# RF_FRONTEND.net
KiCad netlist of a schematic drawn in Altium Designer
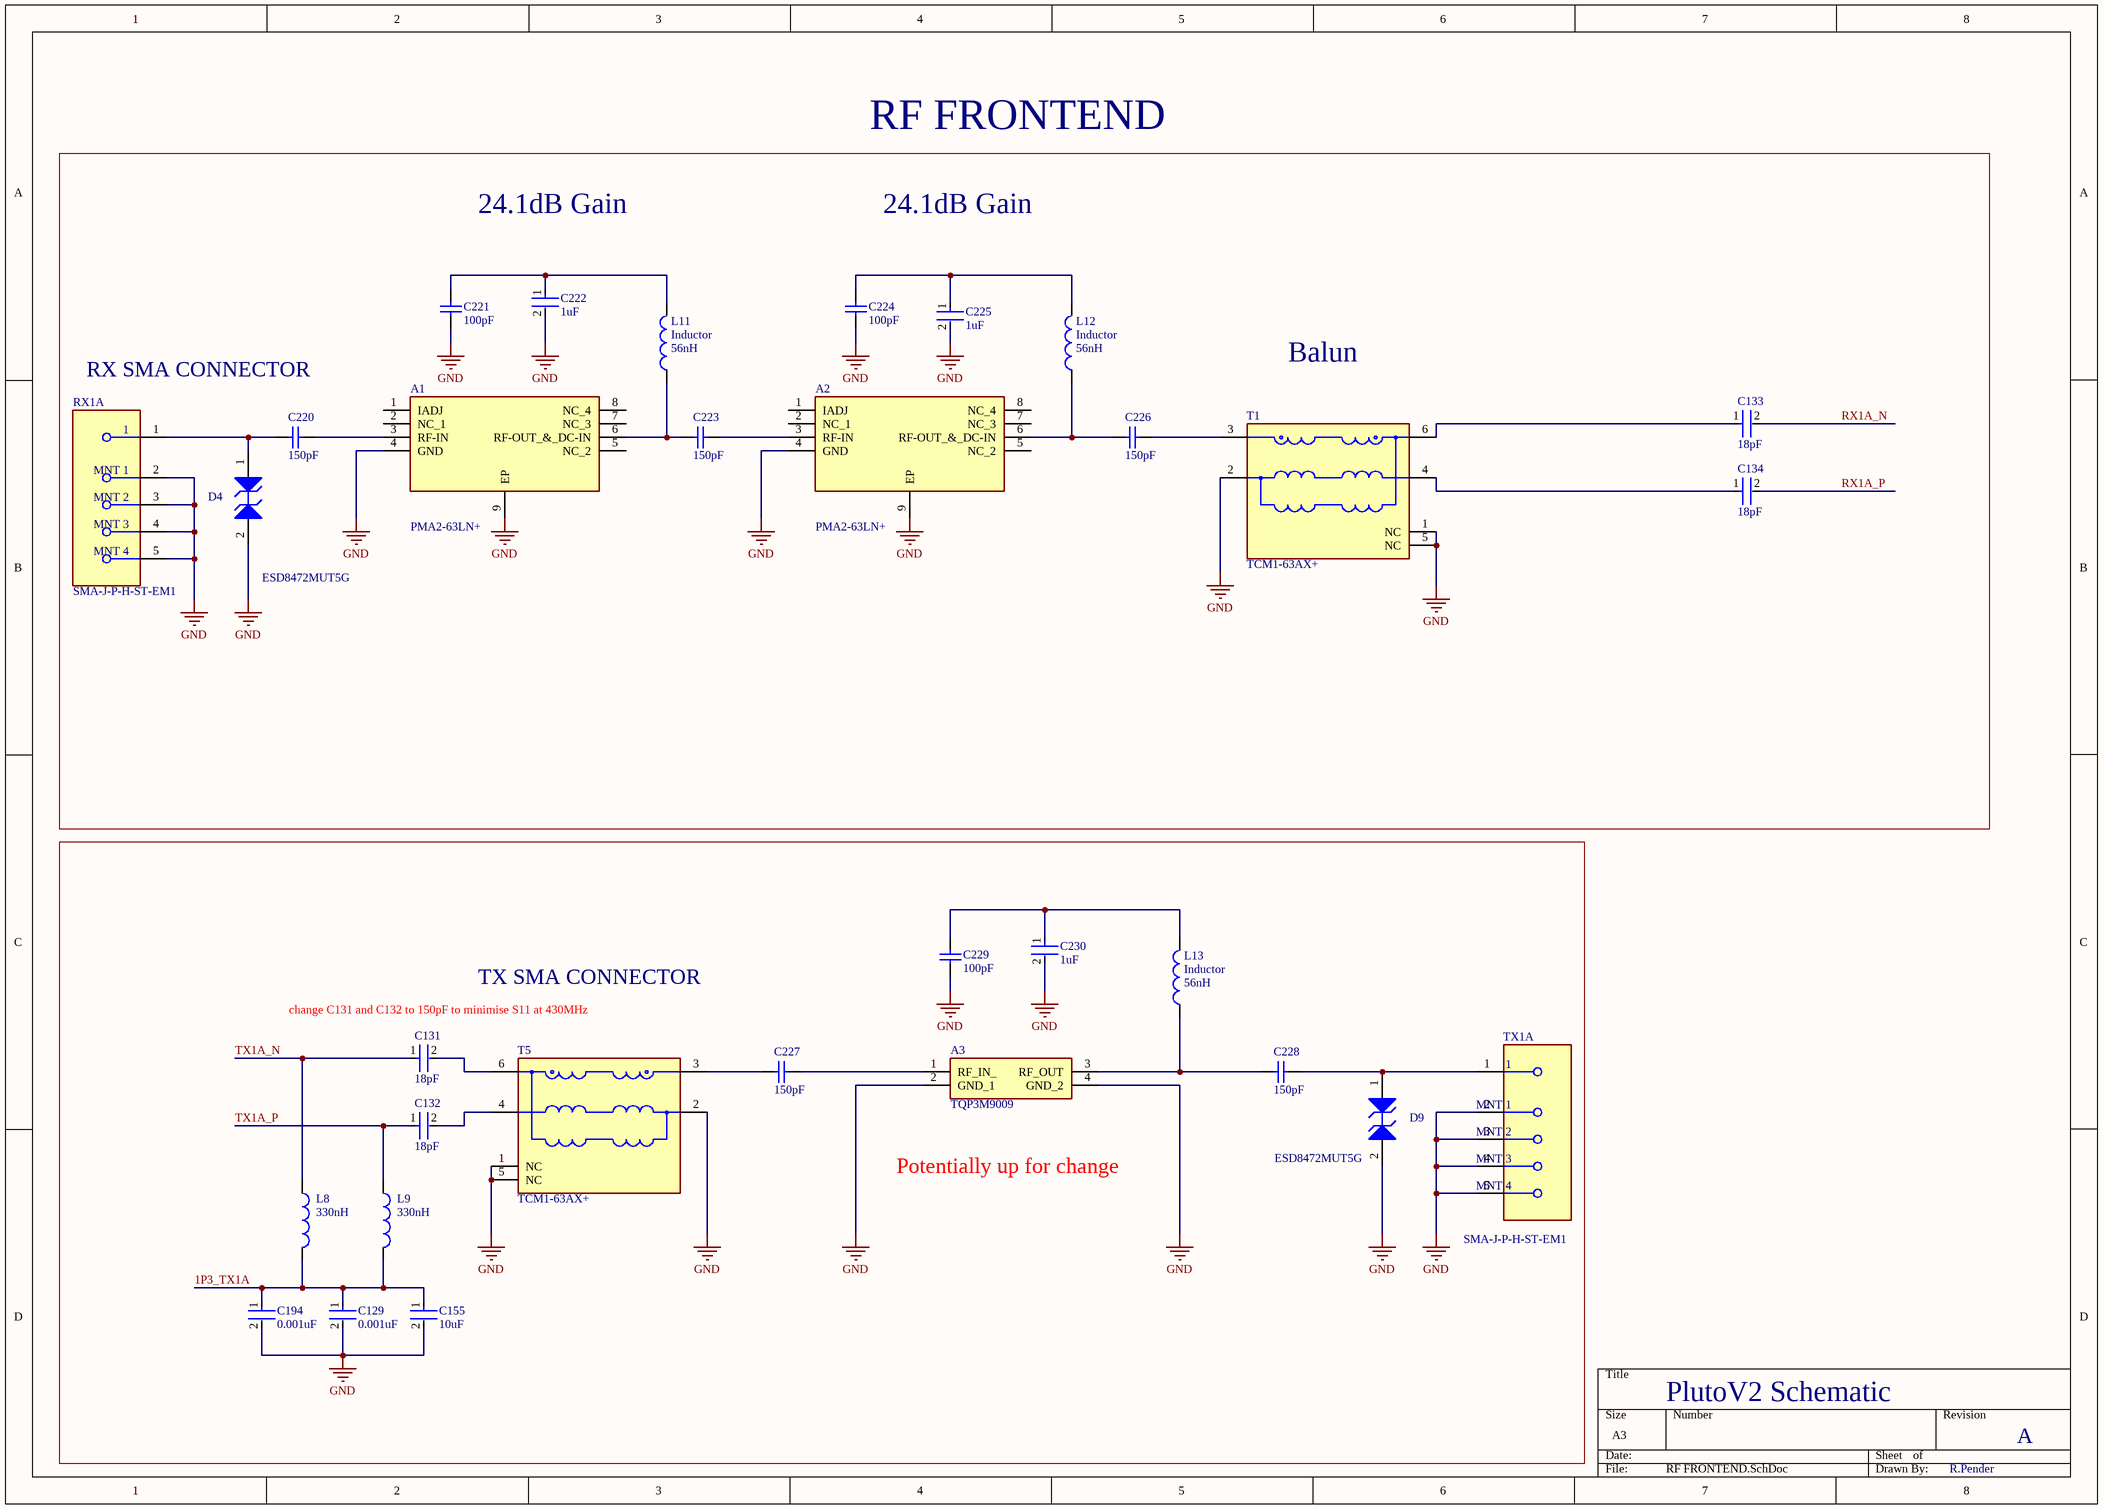
[diagram p0: RF FRONTEND.SchDoc]

(export (version "E")
  (design (tool "Eeschema 10.0.6"))
  (components
    (comp (ref "A1")
      (value "PMA2-63LN+")
      (footprint "SamacSys:SON50P200X200X105-9N")
      (description "Integrated Circuit")
      (libsource (lib "*") (part "PMA2-63LN+"))
    )
    (comp (ref "A2")
      (value "PMA2-63LN+")
      (footprint "SamacSys:SON50P200X200X105-9N")
      (description "Integrated Circuit")
      (libsource (lib "*") (part "PMA2-63LN+"))
    )
    (comp (ref "A3")
      (value "TQP3M9009")
      (footprint "SamacSys:TQP3M9009")
      (description "Integrated Circuit")
      (libsource (lib "*") (part "TQP3M9009"))
    )
    (comp (ref "C129")
      (value "0.001uF")
      (footprint "FP-GRM033-0_03-MFG")
      (description "Chip Multilayer Ceramic Capacitors for General Purpose, 0201, 1000pF, X7R, 15%, 10%, 25V")
      (fields (field (name "TOLERANCE") "10%") (field (name "VOLTAGE") "25V"))
      (libsource (lib "Altium Content Vault") (part "b4654b650e69147ec39a6b967a45e02"))
    )
    (comp (ref "C131")
      (value "18pF")
      (footprint "FP-GRM033-0_03-IPC_A")
      (description "Chip Multilayer Ceramic Capacitors for General Purpose, 0201, 18pF, C0G, 30ppm/°C, 5%, 50V")
      (fields (field (name "TOLERANCE") "5%") (field (name "VOLTAGE") "50V"))
      (libsource (lib "Altium Content Vault") (part "b4654b650e69147ec39a6b967a45e02"))
    )
    (comp (ref "C132")
      (value "18pF")
      (footprint "FP-GRM033-0_03-IPC_A")
      (description "Chip Multilayer Ceramic Capacitors for General Purpose, 0201, 18pF, C0G, 30ppm/°C, 5%, 50V")
      (fields (field (name "TOLERANCE") "5%") (field (name "VOLTAGE") "50V"))
      (libsource (lib "Altium Content Vault") (part "b4654b650e69147ec39a6b967a45e02"))
    )
    (comp (ref "C133")
      (value "18pF")
      (footprint "FP-GRM033-0_03-IPC_A")
      (description "Chip Multilayer Ceramic Capacitors for General Purpose, 0201, 18pF, C0G, 30ppm/°C, 5%, 50V")
      (fields (field (name "TOLERANCE") "5%") (field (name "VOLTAGE") "50V"))
      (libsource (lib "Altium Content Vault") (part "b4654b650e69147ec39a6b967a45e02"))
    )
    (comp (ref "C134")
      (value "18pF")
      (footprint "FP-GRM033-0_03-IPC_A")
      (description "Chip Multilayer Ceramic Capacitors for General Purpose, 0201, 18pF, C0G, 30ppm/°C, 5%, 50V")
      (fields (field (name "TOLERANCE") "5%") (field (name "VOLTAGE") "50V"))
      (libsource (lib "Altium Content Vault") (part "b4654b650e69147ec39a6b967a45e02"))
    )
    (comp (ref "C155")
      (value "10uF")
      (footprint "FP-GRM188-0_1-e0_2_0_55-IPC_C")
      (description "Chip Multilayer Ceramic Capacitors for General Purpose, 0603, 10uF, X5R, 15%, 20%, 6.3V")
      (fields (field (name "VOLTAGE") "6.3V") (field (name "TOLERANCE") "20%"))
      (libsource (lib "Altium Content Vault") (part "02cd4be3c70576c341d710602a673aa"))
    )
    (comp (ref "C194")
      (value "0.001uF")
      (footprint "FP-GRM033-0_03-MFG")
      (description "Chip Multilayer Ceramic Capacitors for General Purpose, 0201, 1000pF, X7R, 15%, 10%, 25V")
      (fields (field (name "TOLERANCE") "10%") (field (name "VOLTAGE") "25V"))
      (libsource (lib "Altium Content Vault") (part "b4654b650e69147ec39a6b967a45e02"))
    )
    (comp (ref "C220")
      (value "150pF")
      (footprint "CAPC1005X55X25ML05T10")
      (fields (field (name "MANUFACTURER") "Murata") (field (name "PART NUMBER") "GRM1555C1H151JA01D"))
      (libsource (lib "Altium Content Vault") (part "CAP"))
    )
    (comp (ref "C221")
      (value "100pF")
      (footprint "CAPC1005X55X25ML05T10")
      (fields (field (name "MANUFACTURER") "Murata") (field (name "PART NUMBER") "GRM1555C1H101JA01D"))
      (libsource (lib "Altium Content Vault") (part "CAP"))
    )
    (comp (ref "C222")
      (value "1uF")
      (footprint "FP-GRM155-0_05-IPC_B")
      (description "Chip Multilayer Ceramic Capacitors for General Purpose, 0402, 1.0uF, X5R, 15%, 10%, 25V")
      (fields (field (name "VOLTAGE") "25V") (field (name "TOLERANCE") "10%"))
      (libsource (lib "Altium Content Vault") (part "02cd4be3c70576c341d710602a673aa"))
    )
    (comp (ref "C223")
      (value "150pF")
      (footprint "CAPC1005X55X25ML05T10")
      (fields (field (name "MANUFACTURER") "Murata") (field (name "PART NUMBER") "GRM1555C1H151JA01D"))
      (libsource (lib "Altium Content Vault") (part "CAP"))
    )
    (comp (ref "C224")
      (value "100pF")
      (footprint "CAPC1005X55X25ML05T10")
      (fields (field (name "MANUFACTURER") "Murata") (field (name "PART NUMBER") "GRM1555C1H101JA01D"))
      (libsource (lib "Altium Content Vault") (part "CAP"))
    )
    (comp (ref "C225")
      (value "1uF")
      (footprint "FP-GRM155-0_05-IPC_B")
      (description "Chip Multilayer Ceramic Capacitors for General Purpose, 0402, 1.0uF, X5R, 15%, 10%, 25V")
      (fields (field (name "VOLTAGE") "25V") (field (name "TOLERANCE") "10%"))
      (libsource (lib "Altium Content Vault") (part "02cd4be3c70576c341d710602a673aa"))
    )
    (comp (ref "C226")
      (value "150pF")
      (footprint "CAPC1005X55X25LL05T10")
      (fields (field (name "MANUFACTURER") "Murata") (field (name "PART NUMBER") "GRM1555C1H151JA01D"))
      (libsource (lib "Altium Content Vault") (part "CAP"))
    )
    (comp (ref "C227")
      (value "150pF")
      (footprint "CAPC1005X55X25LL05T10")
      (fields (field (name "MANUFACTURER") "Murata") (field (name "PART NUMBER") "GRM1555C1H151JA01D"))
      (libsource (lib "Altium Content Vault") (part "CAP"))
    )
    (comp (ref "C228")
      (value "150pF")
      (footprint "CAPC1005X55X25LL05T10")
      (fields (field (name "MANUFACTURER") "Murata") (field (name "PART NUMBER") "GRM1555C1H151JA01D"))
      (libsource (lib "Altium Content Vault") (part "CAP"))
    )
    (comp (ref "C229")
      (value "100pF")
      (footprint "CAPC1005X55X25ML05T10")
      (fields (field (name "MANUFACTURER") "Murata") (field (name "PART NUMBER") "GRM1555C1H101JA01D"))
      (libsource (lib "Altium Content Vault") (part "CAP"))
    )
    (comp (ref "C230")
      (value "1uF")
      (footprint "FP-GRM155-0_05-IPC_B")
      (description "Chip Multilayer Ceramic Capacitors for General Purpose, 0402, 1.0uF, X5R, 15%, 10%, 25V")
      (fields (field (name "VOLTAGE") "25V") (field (name "TOLERANCE") "10%"))
      (libsource (lib "Altium Content Vault") (part "02cd4be3c70576c341d710602a673aa"))
    )
    (comp (ref "D4")
      (value "ESD8472MUT5G")
      (footprint "ONSC-X3DFN-2-152AF-01_V")
      (fields (field (name "MANUFACTURER") "On Semiconductor"))
      (libsource (lib "Altium Content Vault") (part "ONSC-A1A2-2"))
    )
    (comp (ref "D9")
      (value "ESD8472MUT5G")
      (footprint "ONSC-X3DFN-2-152AF-01_V")
      (fields (field (name "MANUFACTURER") "On Semiconductor"))
      (libsource (lib "Altium Content Vault") (part "ONSC-A1A2-2"))
    )
    (comp (ref "L8")
      (value "330nH")
      (footprint "INDC2317X140N")
      (description "Inductor")
      (fields (field (name "PUBLISHER") "Altium Limited"))
      (libsource (lib "Miscellaneous Devices") (part "Inductor"))
    )
    (comp (ref "L9")
      (value "330nH")
      (footprint "INDC2317X140N")
      (description "Inductor")
      (fields (field (name "PUBLISHER") "Altium Limited"))
      (libsource (lib "Miscellaneous Devices") (part "Inductor"))
    )
    (comp (ref "L11")
      (value "Inductor")
      (footprint "0402-A")
      (fields (field (name "ALTIUM_VALUE") "56nH") (field (name "PUBLISHER") "Altium Limited"))
      (libsource (lib "Miscellaneous Devices") (part "Inductor"))
    )
    (comp (ref "L12")
      (value "Inductor")
      (footprint "0402-A")
      (fields (field (name "ALTIUM_VALUE") "56nH") (field (name "PUBLISHER") "Altium Limited"))
      (libsource (lib "Miscellaneous Devices") (part "Inductor"))
    )
    (comp (ref "L13")
      (value "Inductor")
      (footprint "0402-A")
      (fields (field (name "ALTIUM_VALUE") "56nH") (field (name "PUBLISHER") "Altium Limited"))
      (libsource (lib "Miscellaneous Devices") (part "Inductor"))
    )
    (comp (ref "RX1A")
      (value "SMA-J-P-H-ST-EM1")
      (footprint "FP-SMA-J-P-H-ST-EM1-MFG")
      (description "CONN SMA JACK STR 50OHM EDGE MNT")
      (libsource (lib "Altium Content Vault") (part "c65b8a639cdaef1819ea20b5466f8fa"))
    )
    (comp (ref "T1")
      (value "TCM1-63AX+")
      (footprint "FP-TCM1-63AX+-MFG")
      (description "1:1 CORE & WIRE Transformer, 10 - 6000 MHz, 50Ω")
      (fields
        (field (name "MANUFACTURER") "Mini-Circuits")
        (field (name "OCTOPART") "https://octopart.com/tcm1-63ax%2B-mini-circuits-107315723")
      )
      (libsource (lib "") (part "572340aedd709dbafee1a1d3331a406_1"))
    )
    (comp (ref "T5")
      (value "TCM1-63AX+")
      (footprint "FP-TCM1-63AX+-MFG")
      (description "1:1 CORE & WIRE Transformer, 10 - 6000 MHz, 50Ω")
      (fields
        (field (name "MANUFACTURER") "Mini-Circuits")
        (field (name "OCTOPART") "https://octopart.com/tcm1-63ax%2B-mini-circuits-107315723")
      )
      (libsource (lib "Altium Content Vault") (part "572340aedd709dbafee1a1d3331a406"))
    )
    (comp (ref "TX1A")
      (value "SMA-J-P-H-ST-EM1")
      (footprint "FP-SMA-J-P-H-ST-EM1-MFG")
      (description "CONN SMA JACK STR 50OHM EDGE MNT")
      (libsource (lib "") (part "c65b8a639cdaef1819ea20b5466f8fa_1"))
    )
  )
  (nets
    (net (code "1") (name "/1P3_TX1A") (class "Default")
      (node (ref "C129") (pin "1") (pinfunction "1_1") (pintype "passive"))
      (node (ref "C155") (pin "1") (pinfunction "1_1") (pintype "passive"))
      (node (ref "C194") (pin "1") (pinfunction "1_1") (pintype "passive"))
      (node (ref "L8") (pin "2") (pinfunction "2_2") (pintype "passive"))
      (node (ref "L9") (pin "2") (pinfunction "2_2") (pintype "passive"))
    )
    (net (code "2") (name "/RX1A_N") (class "Default")
      (node (ref "C133") (pin "2") (pinfunction "2_2") (pintype "passive"))
    )
    (net (code "3") (name "/RX1A_P") (class "Default")
      (node (ref "C134") (pin "2") (pinfunction "2_2") (pintype "passive"))
    )
    (net (code "4") (name "/TX1A_N") (class "Default")
      (node (ref "C131") (pin "1") (pinfunction "1_1") (pintype "passive"))
      (node (ref "L8") (pin "1") (pinfunction "1_1") (pintype "passive"))
    )
    (net (code "5") (name "/TX1A_P") (class "Default")
      (node (ref "C132") (pin "1") (pinfunction "1_1") (pintype "passive"))
      (node (ref "L9") (pin "1") (pinfunction "1_1") (pintype "passive"))
    )
    (net (code "6") (name "GND") (class "Default")
      (node (ref "A1") (pin "4") (pinfunction "GND_4") (pintype "passive"))
      (node (ref "A1") (pin "9") (pinfunction "EP_9") (pintype "passive"))
      (node (ref "A2") (pin "4") (pinfunction "GND_4") (pintype "passive"))
      (node (ref "A2") (pin "9") (pinfunction "EP_9") (pintype "passive"))
      (node (ref "A3") (pin "2") (pinfunction "GND_1_2") (pintype "passive"))
      (node (ref "A3") (pin "4") (pinfunction "GND_2_4") (pintype "passive"))
      (node (ref "C129") (pin "2") (pinfunction "2_2") (pintype "passive"))
      (node (ref "C155") (pin "2") (pinfunction "2_2") (pintype "passive"))
      (node (ref "C194") (pin "2") (pinfunction "2_2") (pintype "passive"))
      (node (ref "C221") (pin "2") (pinfunction "2_2") (pintype "passive"))
      (node (ref "C222") (pin "2") (pinfunction "2_2") (pintype "passive"))
      (node (ref "C224") (pin "2") (pinfunction "2_2") (pintype "passive"))
      (node (ref "C225") (pin "2") (pinfunction "2_2") (pintype "passive"))
      (node (ref "C229") (pin "2") (pinfunction "2_2") (pintype "passive"))
      (node (ref "C230") (pin "2") (pinfunction "2_2") (pintype "passive"))
      (node (ref "D4") (pin "2") (pinfunction "A2_2") (pintype "passive"))
      (node (ref "D9") (pin "2") (pinfunction "A2_2") (pintype "passive"))
      (node (ref "RX1A") (pin "2") (pinfunction "MNT_1_2") (pintype "passive"))
      (node (ref "RX1A") (pin "3") (pinfunction "MNT_2_3") (pintype "passive"))
      (node (ref "RX1A") (pin "4") (pinfunction "MNT_3_4") (pintype "passive"))
      (node (ref "RX1A") (pin "5") (pinfunction "MNT_4_5") (pintype "passive"))
      (node (ref "T1") (pin "1") (pinfunction "NC_1") (pintype "passive"))
      (node (ref "T1") (pin "2") (pinfunction "GND_2") (pintype "passive"))
      (node (ref "T1") (pin "5") (pinfunction "NC_5") (pintype "passive"))
      (node (ref "T5") (pin "1") (pinfunction "NC_1") (pintype "passive"))
      (node (ref "T5") (pin "2") (pinfunction "GND_2") (pintype "passive"))
      (node (ref "T5") (pin "5") (pinfunction "NC_5") (pintype "passive"))
      (node (ref "TX1A") (pin "2") (pinfunction "MNT_1_2") (pintype "passive"))
      (node (ref "TX1A") (pin "3") (pinfunction "MNT_2_3") (pintype "passive"))
      (node (ref "TX1A") (pin "4") (pinfunction "MNT_3_4") (pintype "passive"))
      (node (ref "TX1A") (pin "5") (pinfunction "MNT_4_5") (pintype "passive"))
    )
    (net (code "7") (name "Net-(A1-RF-IN)") (class "Default")
      (node (ref "A1") (pin "3") (pinfunction "RF-IN_3") (pintype "passive"))
      (node (ref "C220") (pin "2") (pinfunction "2_2") (pintype "passive"))
    )
    (net (code "8") (name "Net-(A1-RF-OUT_&_DC-IN)") (class "Default")
      (node (ref "A1") (pin "6") (pinfunction "RF-OUT_&_DC-IN_6") (pintype "passive"))
      (node (ref "C223") (pin "1") (pinfunction "1_1") (pintype "passive"))
      (node (ref "L11") (pin "1") (pinfunction "1_1") (pintype "passive"))
    )
    (net (code "9") (name "Net-(A2-RF-IN)") (class "Default")
      (node (ref "A2") (pin "3") (pinfunction "RF-IN_3") (pintype "passive"))
      (node (ref "C223") (pin "2") (pinfunction "2_2") (pintype "passive"))
    )
    (net (code "10") (name "Net-(A2-RF-OUT_&_DC-IN)") (class "Default")
      (node (ref "A2") (pin "6") (pinfunction "RF-OUT_&_DC-IN_6") (pintype "passive"))
      (node (ref "C226") (pin "1") (pinfunction "1_1") (pintype "passive"))
      (node (ref "L12") (pin "1") (pinfunction "1_1") (pintype "passive"))
    )
    (net (code "11") (name "Net-(A3-RF_IN_)") (class "Default")
      (node (ref "A3") (pin "1") (pinfunction "RF_IN__1") (pintype "passive"))
      (node (ref "C227") (pin "2") (pinfunction "2_2") (pintype "passive"))
    )
    (net (code "12") (name "Net-(A3-RF_OUT)") (class "Default")
      (node (ref "A3") (pin "3") (pinfunction "RF_OUT_3") (pintype "passive"))
      (node (ref "C228") (pin "1") (pinfunction "1_1") (pintype "passive"))
      (node (ref "L13") (pin "1") (pinfunction "1_1") (pintype "passive"))
    )
    (net (code "13") (name "Net-(C221-Pad1)") (class "Default")
      (node (ref "C221") (pin "1") (pinfunction "1_1") (pintype "passive"))
      (node (ref "C222") (pin "1") (pinfunction "1_1") (pintype "passive"))
      (node (ref "L11") (pin "2") (pinfunction "2_2") (pintype "passive"))
    )
    (net (code "14") (name "Net-(C224-Pad1)") (class "Default")
      (node (ref "C224") (pin "1") (pinfunction "1_1") (pintype "passive"))
      (node (ref "C225") (pin "1") (pinfunction "1_1") (pintype "passive"))
      (node (ref "L12") (pin "2") (pinfunction "2_2") (pintype "passive"))
    )
    (net (code "15") (name "Net-(C229-Pad1)") (class "Default")
      (node (ref "C229") (pin "1") (pinfunction "1_1") (pintype "passive"))
      (node (ref "C230") (pin "1") (pinfunction "1_1") (pintype "passive"))
      (node (ref "L13") (pin "2") (pinfunction "2_2") (pintype "passive"))
    )
    (net (code "16") (name "Net-(D4-A1)") (class "Default")
      (node (ref "C220") (pin "1") (pinfunction "1_1") (pintype "passive"))
      (node (ref "D4") (pin "1") (pinfunction "A1_1") (pintype "passive"))
      (node (ref "RX1A") (pin "1") (pinfunction "1_1") (pintype "passive"))
    )
    (net (code "17") (name "Net-(D9-A1)") (class "Default")
      (node (ref "C228") (pin "2") (pinfunction "2_2") (pintype "passive"))
      (node (ref "D9") (pin "1") (pinfunction "A1_1") (pintype "passive"))
      (node (ref "TX1A") (pin "1") (pinfunction "1_1") (pintype "passive"))
    )
    (net (code "18") (name "Net-(T1-PRIMARY_DOT)") (class "Default")
      (node (ref "C226") (pin "2") (pinfunction "2_2") (pintype "passive"))
      (node (ref "T1") (pin "3") (pinfunction "PRIMARY_DOT_3") (pintype "passive"))
    )
    (net (code "19") (name "Net-(T1-SECONDARY)") (class "Default")
      (node (ref "C134") (pin "1") (pinfunction "1_1") (pintype "passive"))
      (node (ref "T1") (pin "4") (pinfunction "SECONDARY_4") (pintype "passive"))
    )
    (net (code "20") (name "Net-(T1-SECONDARY_DOT)") (class "Default")
      (node (ref "C133") (pin "1") (pinfunction "1_1") (pintype "passive"))
      (node (ref "T1") (pin "6") (pinfunction "SECONDARY_DOT_6") (pintype "passive"))
    )
    (net (code "21") (name "Net-(T5-PRIMARY_DOT)") (class "Default")
      (node (ref "C227") (pin "1") (pinfunction "1_1") (pintype "passive"))
      (node (ref "T5") (pin "3") (pinfunction "PRIMARY_DOT_3") (pintype "passive"))
    )
    (net (code "22") (name "Net-(T5-SECONDARY)") (class "Default")
      (node (ref "C132") (pin "2") (pinfunction "2_2") (pintype "passive"))
      (node (ref "T5") (pin "4") (pinfunction "SECONDARY_4") (pintype "passive"))
    )
    (net (code "23") (name "Net-(T5-SECONDARY_DOT)") (class "Default")
      (node (ref "C131") (pin "2") (pinfunction "2_2") (pintype "passive"))
      (node (ref "T5") (pin "6") (pinfunction "SECONDARY_DOT_6") (pintype "passive"))
    )
    (net (code "24") (name "unconnected-(A1-IADJ-Pad1)") (class "Default")
      (node (ref "A1") (pin "1") (pinfunction "IADJ_1") (pintype "passive"))
    )
    (net (code "25") (name "unconnected-(A1-NC_1-Pad2)") (class "Default")
      (node (ref "A1") (pin "2") (pinfunction "NC_1_2") (pintype "passive"))
    )
    (net (code "26") (name "unconnected-(A1-NC_2-Pad5)") (class "Default")
      (node (ref "A1") (pin "5") (pinfunction "NC_2_5") (pintype "passive"))
    )
    (net (code "27") (name "unconnected-(A1-NC_3-Pad7)") (class "Default")
      (node (ref "A1") (pin "7") (pinfunction "NC_3_7") (pintype "passive"))
    )
    (net (code "28") (name "unconnected-(A1-NC_4-Pad8)") (class "Default")
      (node (ref "A1") (pin "8") (pinfunction "NC_4_8") (pintype "passive"))
    )
    (net (code "29") (name "unconnected-(A2-IADJ-Pad1)") (class "Default")
      (node (ref "A2") (pin "1") (pinfunction "IADJ_1") (pintype "passive"))
    )
    (net (code "30") (name "unconnected-(A2-NC_1-Pad2)") (class "Default")
      (node (ref "A2") (pin "2") (pinfunction "NC_1_2") (pintype "passive"))
    )
    (net (code "31") (name "unconnected-(A2-NC_2-Pad5)") (class "Default")
      (node (ref "A2") (pin "5") (pinfunction "NC_2_5") (pintype "passive"))
    )
    (net (code "32") (name "unconnected-(A2-NC_3-Pad7)") (class "Default")
      (node (ref "A2") (pin "7") (pinfunction "NC_3_7") (pintype "passive"))
    )
    (net (code "33") (name "unconnected-(A2-NC_4-Pad8)") (class "Default")
      (node (ref "A2") (pin "8") (pinfunction "NC_4_8") (pintype "passive"))
    )
  )
)
